# H22R2x_Frontend_1.net
KiCad netlist of a schematic drawn in Altium Designer
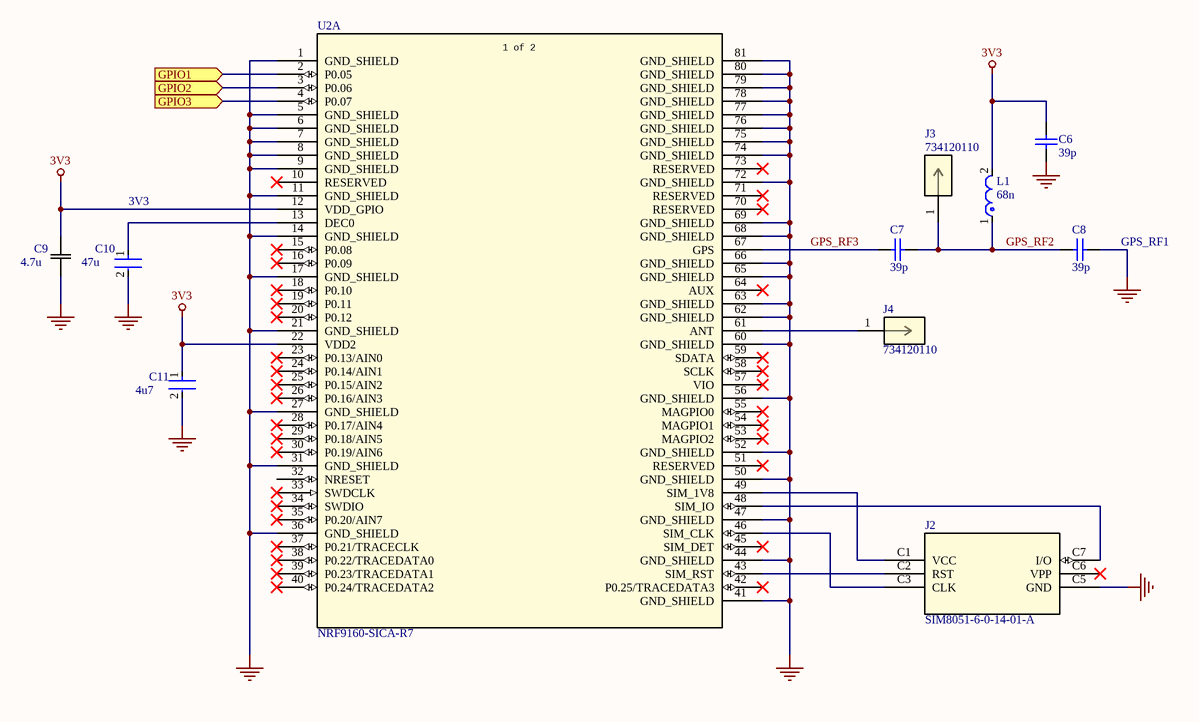
[diagram p0: H22R2x_Frontend 1.SchDoc]

(export (version "E")
  (design (tool "Eeschema 10.0.6"))
  (components
    (comp (ref "C6")
      (value "39p")
      (footprint "CAPC1005X56X25ML10T15")
      (description "04023A390KAT2A")
      (fields (field (name "MANUFACTURER") "AVX Interconnect / Elco"))
      (libsource (lib "Altium Content Vault") (part "CAP"))
    )
    (comp (ref "C7")
      (value "39p")
      (footprint "CAPC1005X56X25ML10T15")
      (description "04023A390KAT2A")
      (fields (field (name "MANUFACTURER") "AVX Interconnect / Elco"))
      (libsource (lib "Altium Content Vault") (part "CAP"))
    )
    (comp (ref "C8")
      (value "39p")
      (footprint "CAPC1005X56X25ML10T15")
      (description "04023A390KAT2A")
      (fields (field (name "MANUFACTURER") "AVX Interconnect / Elco"))
      (libsource (lib "Altium Content Vault") (part "CAP"))
    )
    (comp (ref "C9")
      (value "4.7u")
      (footprint "CAP_CL10_SAM")
      (description "4.7 µF ±10% 6.3V Ceramic Capacitor X5R 0603 (1608 Metric)")
      (fields
        (field (name "MANUFACTURER_PART_NUMBER") "CL10A475KQ8NNNC")
        (field (name "COPYRIGHT") "Copyright (C) 2025 Ultra Librarian. All rights reserved.")
      )
      (libsource (lib "Tyme Hopkins") (part "CL10A475KQ8NNNC"))
    )
    (comp (ref "C10")
      (value "47u")
      (footprint "FP-GRM21B-0_2-e0_2_0_7-IPC_B")
      (description "Chip Multilayer Ceramic Capacitors for General Purpose, 0805, 47uF, X5R, 15%, 20%, 6.3V")
      (fields (field (name "TOLERANCE") "20%"))
      (libsource (lib "Altium Content Vault") (part "b4654b650e69147ec39a6b967a45e02"))
    )
    (comp (ref "C11")
      (value "4u7")
      (footprint "FP-0603-L_1_6_0_15-W_0_8-MFG")
      (description "Ceramic Capacitor General Use 4.7uF ±10% 10V X6S 0603")
      (fields (field (name "TOLERANCE") "10%"))
      (libsource (lib "Altium Content Vault") (part "11868f565c42a9108669ba33697ecf6"))
    )
    (comp (ref "J2")
      (value "SIM8051-6-0-14-01-A")
      (footprint "SIM8051-6-0-14-01-A_GCT")
      (description "Description")
      (fields (field (name "COPYRIGHT") "Copyright (C) 2025 Ultra Librarian. All rights reserved."))
      (libsource (lib "Tyme Hopkins") (part "SIM8051-6-0-14-01-A"))
    )
    (comp (ref "J3")
      (value "734120110")
      (footprint "CONN_73412-0110_MOL")
      (description "MCRF Jack, Straight, PCB Receptacle, Surface Mount, 1.25mm Mounted Height, 50 Ohms")
      (fields (field (name "COPYRIGHT") "Copyright (C) 2025 Ultra Librarian. All rights reserved."))
      (libsource (lib "Tyme Hopkins") (part "734120110"))
    )
    (comp (ref "J4")
      (value "734120110")
      (footprint "CONN_73412-0110_MOL")
      (description "MCRF Jack, Straight, PCB Receptacle, Surface Mount, 1.25mm Mounted Height, 50 Ohms")
      (fields (field (name "COPYRIGHT") "Copyright (C) 2025 Ultra Librarian. All rights reserved."))
      (libsource (lib "") (part "734120110_1"))
    )
    (comp (ref "L1")
      (value "68n")
      (footprint "FP-LQG18HH_00-MFG")
      (description "Multilayer type RF Inductor 68nH ±5% 0.8Ω 400mA 0603\r\n\r\nLQG18HN68NJ00D")
      (fields (field (name "TOLERANCE") "5%"))
      (libsource (lib "Altium Content Vault") (part "4cc4b267dca4c8e51f7102f422741d8"))
    )
    (comp (ref "U2")
      (value "NRF9160-SICA-R7")
      (footprint "LGA127_16p00X10p50_nRF9160_NOR")
      (description "Description")
      (fields (field (name "COPYRIGHT") "Copyright (C) 2025 Ultra Librarian. All rights reserved."))
      (libsource (lib "Tyme Hopkins") (part "NRF9160-SICA-R7"))
    )
  )
  (nets
    (net (code "1") (name "/GPIO1") (class "Default")
      (node (ref "U2") (pin "2") (pinfunction "P0.05_2") (pintype "bidirectional"))
    )
    (net (code "2") (name "/GPIO2") (class "Default")
      (node (ref "U2") (pin "3") (pinfunction "P0.06_3") (pintype "bidirectional"))
    )
    (net (code "3") (name "/GPIO3") (class "Default")
      (node (ref "U2") (pin "4") (pinfunction "P0.07_4") (pintype "bidirectional"))
    )
    (net (code "4") (name "/GPS_RF2") (class "Default")
      (node (ref "C7") (pin "2") (pinfunction "2_2") (pintype "passive"))
      (node (ref "C8") (pin "1") (pinfunction "1_1") (pintype "passive"))
      (node (ref "J3") (pin "1") (pinfunction "1_1") (pintype "passive"))
      (node (ref "L1") (pin "1") (pinfunction "1_1") (pintype "passive"))
    )
    (net (code "5") (name "/GPS_RF3") (class "Default")
      (node (ref "C7") (pin "1") (pinfunction "1_1") (pintype "passive"))
      (node (ref "U2") (pin "67") (pinfunction "GPS_67") (pintype "passive"))
    )
    (net (code "6") (name "3V3") (class "Default")
      (node (ref "C11") (pin "1") (pinfunction "1_1") (pintype "passive"))
      (node (ref "C6") (pin "2") (pinfunction "2_2") (pintype "passive"))
      (node (ref "C9") (pin "2") (pinfunction "2_2") (pintype "passive"))
      (node (ref "L1") (pin "2") (pinfunction "2_2") (pintype "passive"))
      (node (ref "U2") (pin "12") (pinfunction "VDD_GPIO_12") (pintype "power_in"))
      (node (ref "U2") (pin "22") (pinfunction "VDD2_22") (pintype "power_in"))
    )
    (net (code "7") (name "GND") (class "Default")
      (node (ref "C10") (pin "2") (pinfunction "2_2") (pintype "passive"))
      (node (ref "C11") (pin "2") (pinfunction "2_2") (pintype "passive"))
      (node (ref "C6") (pin "1") (pinfunction "1_1") (pintype "passive"))
      (node (ref "C8") (pin "2") (pinfunction "2_2") (pintype "passive"))
      (node (ref "C9") (pin "1") (pinfunction "1_1") (pintype "passive"))
      (node (ref "J2") (pin "C5") (pinfunction "GND_C5") (pintype "power_in"))
      (node (ref "U2") (pin "1") (pinfunction "GND_SHIELD_1") (pintype "power_in"))
      (node (ref "U2") (pin "11") (pinfunction "GND_SHIELD_11") (pintype "power_in"))
      (node (ref "U2") (pin "14") (pinfunction "GND_SHIELD_14") (pintype "power_in"))
      (node (ref "U2") (pin "17") (pinfunction "GND_SHIELD_17") (pintype "power_in"))
      (node (ref "U2") (pin "21") (pinfunction "GND_SHIELD_21") (pintype "power_in"))
      (node (ref "U2") (pin "27") (pinfunction "GND_SHIELD_27") (pintype "power_in"))
      (node (ref "U2") (pin "31") (pinfunction "GND_SHIELD_31") (pintype "power_in"))
      (node (ref "U2") (pin "36") (pinfunction "GND_SHIELD_36") (pintype "power_in"))
      (node (ref "U2") (pin "41") (pinfunction "GND_SHIELD_41") (pintype "power_in"))
      (node (ref "U2") (pin "44") (pinfunction "GND_SHIELD_44") (pintype "power_in"))
      (node (ref "U2") (pin "47") (pinfunction "GND_SHIELD_47") (pintype "power_in"))
      (node (ref "U2") (pin "5") (pinfunction "GND_SHIELD_5") (pintype "power_in"))
      (node (ref "U2") (pin "50") (pinfunction "GND_SHIELD_50") (pintype "power_in"))
      (node (ref "U2") (pin "52") (pinfunction "GND_SHIELD_52") (pintype "power_in"))
      (node (ref "U2") (pin "56") (pinfunction "GND_SHIELD_56") (pintype "power_in"))
      (node (ref "U2") (pin "6") (pinfunction "GND_SHIELD_6") (pintype "power_in"))
      (node (ref "U2") (pin "60") (pinfunction "GND_SHIELD_60") (pintype "power_in"))
      (node (ref "U2") (pin "62") (pinfunction "GND_SHIELD_62") (pintype "power_in"))
      (node (ref "U2") (pin "63") (pinfunction "GND_SHIELD_63") (pintype "power_in"))
      (node (ref "U2") (pin "65") (pinfunction "GND_SHIELD_65") (pintype "power_in"))
      (node (ref "U2") (pin "66") (pinfunction "GND_SHIELD_66") (pintype "power_in"))
      (node (ref "U2") (pin "68") (pinfunction "GND_SHIELD_68") (pintype "power_in"))
      (node (ref "U2") (pin "69") (pinfunction "GND_SHIELD_69") (pintype "power_in"))
      (node (ref "U2") (pin "7") (pinfunction "GND_SHIELD_7") (pintype "power_in"))
      (node (ref "U2") (pin "72") (pinfunction "GND_SHIELD_72") (pintype "power_in"))
      (node (ref "U2") (pin "74") (pinfunction "GND_SHIELD_74") (pintype "power_in"))
      (node (ref "U2") (pin "75") (pinfunction "GND_SHIELD_75") (pintype "power_in"))
      (node (ref "U2") (pin "76") (pinfunction "GND_SHIELD_76") (pintype "power_in"))
      (node (ref "U2") (pin "77") (pinfunction "GND_SHIELD_77") (pintype "power_in"))
      (node (ref "U2") (pin "78") (pinfunction "GND_SHIELD_78") (pintype "power_in"))
      (node (ref "U2") (pin "79") (pinfunction "GND_SHIELD_79") (pintype "power_in"))
      (node (ref "U2") (pin "8") (pinfunction "GND_SHIELD_8") (pintype "power_in"))
      (node (ref "U2") (pin "80") (pinfunction "GND_SHIELD_80") (pintype "power_in"))
      (node (ref "U2") (pin "81") (pinfunction "GND_SHIELD_81") (pintype "power_in"))
      (node (ref "U2") (pin "9") (pinfunction "GND_SHIELD_9") (pintype "power_in"))
    )
    (net (code "8") (name "Net-(J2-CLK)") (class "Default")
      (node (ref "J2") (pin "C3") (pinfunction "CLK_C3") (pintype "passive"))
      (node (ref "U2") (pin "46") (pinfunction "SIM_CLK_46") (pintype "bidirectional"))
    )
    (net (code "9") (name "Net-(J2-I{slash}O)") (class "Default")
      (node (ref "J2") (pin "C7") (pinfunction "I/O_C7") (pintype "bidirectional"))
      (node (ref "U2") (pin "48") (pinfunction "SIM_IO_48") (pintype "bidirectional"))
    )
    (net (code "10") (name "Net-(J2-RST)") (class "Default")
      (node (ref "J2") (pin "C2") (pinfunction "RST_C2") (pintype "passive"))
      (node (ref "U2") (pin "43") (pinfunction "SIM_RST_43") (pintype "bidirectional"))
    )
    (net (code "11") (name "Net-(J2-VCC)") (class "Default")
      (node (ref "J2") (pin "C1") (pinfunction "VCC_C1") (pintype "power_in"))
      (node (ref "U2") (pin "49") (pinfunction "SIM_1V8_49") (pintype "power_in"))
    )
    (net (code "12") (name "Net-(U2A-ANT)") (class "Default")
      (node (ref "J4") (pin "1") (pinfunction "1_1") (pintype "passive"))
      (node (ref "U2") (pin "61") (pinfunction "ANT_61") (pintype "passive"))
    )
    (net (code "13") (name "Net-(U2A-DEC0)") (class "Default")
      (node (ref "C10") (pin "1") (pinfunction "1_1") (pintype "passive"))
      (node (ref "U2") (pin "13") (pinfunction "DEC0_13") (pintype "power_in"))
    )
    (net (code "14") (name "unconnected-(J2-VPP-PadC6)") (class "Default")
      (node (ref "J2") (pin "C6") (pinfunction "VPP_C6") (pintype "power_in+no_connect"))
    )
    (net (code "15") (name "unconnected-(U2A-AUX-Pad64)") (class "Default")
      (node (ref "U2") (pin "64") (pinfunction "AUX_64") (pintype "passive+no_connect"))
    )
    (net (code "16") (name "unconnected-(U2A-MAGPIO0-Pad55)") (class "Default")
      (node (ref "U2") (pin "55") (pinfunction "MAGPIO0_55") (pintype "bidirectional+no_connect"))
    )
    (net (code "17") (name "unconnected-(U2A-MAGPIO1-Pad54)") (class "Default")
      (node (ref "U2") (pin "54") (pinfunction "MAGPIO1_54") (pintype "bidirectional+no_connect"))
    )
    (net (code "18") (name "unconnected-(U2A-MAGPIO2-Pad53)") (class "Default")
      (node (ref "U2") (pin "53") (pinfunction "MAGPIO2_53") (pintype "bidirectional+no_connect"))
    )
    (net (code "19") (name "unconnected-(U2A-NRESET-Pad32)") (class "Default")
      (node (ref "U2") (pin "32") (pinfunction "NRESET_32") (pintype "bidirectional"))
    )
    (net (code "20") (name "unconnected-(U2A-P0.08-Pad15)") (class "Default")
      (node (ref "U2") (pin "15") (pinfunction "P0.08_15") (pintype "bidirectional+no_connect"))
    )
    (net (code "21") (name "unconnected-(U2A-P0.09-Pad16)") (class "Default")
      (node (ref "U2") (pin "16") (pinfunction "P0.09_16") (pintype "bidirectional+no_connect"))
    )
    (net (code "22") (name "unconnected-(U2A-P0.10-Pad18)") (class "Default")
      (node (ref "U2") (pin "18") (pinfunction "P0.10_18") (pintype "bidirectional+no_connect"))
    )
    (net (code "23") (name "unconnected-(U2A-P0.11-Pad19)") (class "Default")
      (node (ref "U2") (pin "19") (pinfunction "P0.11_19") (pintype "bidirectional+no_connect"))
    )
    (net (code "24") (name "unconnected-(U2A-P0.12-Pad20)") (class "Default")
      (node (ref "U2") (pin "20") (pinfunction "P0.12_20") (pintype "bidirectional+no_connect"))
    )
    (net (code "25") (name "unconnected-(U2A-P0.13{slash}AIN0-Pad23)") (class "Default")
      (node (ref "U2") (pin "23") (pinfunction "P0.13/AIN0_23") (pintype "bidirectional+no_connect"))
    )
    (net (code "26") (name "unconnected-(U2A-P0.14{slash}AIN1-Pad24)") (class "Default")
      (node (ref "U2") (pin "24") (pinfunction "P0.14/AIN1_24") (pintype "bidirectional+no_connect"))
    )
    (net (code "27") (name "unconnected-(U2A-P0.15{slash}AIN2-Pad25)") (class "Default")
      (node (ref "U2") (pin "25") (pinfunction "P0.15/AIN2_25") (pintype "bidirectional+no_connect"))
    )
    (net (code "28") (name "unconnected-(U2A-P0.16{slash}AIN3-Pad26)") (class "Default")
      (node (ref "U2") (pin "26") (pinfunction "P0.16/AIN3_26") (pintype "bidirectional+no_connect"))
    )
    (net (code "29") (name "unconnected-(U2A-P0.17{slash}AIN4-Pad28)") (class "Default")
      (node (ref "U2") (pin "28") (pinfunction "P0.17/AIN4_28") (pintype "bidirectional+no_connect"))
    )
    (net (code "30") (name "unconnected-(U2A-P0.18{slash}AIN5-Pad29)") (class "Default")
      (node (ref "U2") (pin "29") (pinfunction "P0.18/AIN5_29") (pintype "bidirectional+no_connect"))
    )
    (net (code "31") (name "unconnected-(U2A-P0.19{slash}AIN6-Pad30)") (class "Default")
      (node (ref "U2") (pin "30") (pinfunction "P0.19/AIN6_30") (pintype "bidirectional+no_connect"))
    )
    (net (code "32") (name "unconnected-(U2A-P0.20{slash}AIN7-Pad35)") (class "Default")
      (node (ref "U2") (pin "35") (pinfunction "P0.20/AIN7_35") (pintype "bidirectional+no_connect"))
    )
    (net (code "33") (name "unconnected-(U2A-P0.21{slash}TRACECLK-Pad37)") (class "Default")
      (node (ref "U2") (pin "37") (pinfunction "P0.21/TRACECLK_37") (pintype "bidirectional+no_connect"))
    )
    (net (code "34") (name "unconnected-(U2A-P0.22{slash}TRACEDATA0-Pad38)") (class "Default")
      (node (ref "U2") (pin "38") (pinfunction "P0.22/TRACEDATA0_38") (pintype "bidirectional+no_connect"))
    )
    (net (code "35") (name "unconnected-(U2A-P0.23{slash}TRACEDATA1-Pad39)") (class "Default")
      (node (ref "U2") (pin "39") (pinfunction "P0.23/TRACEDATA1_39") (pintype "bidirectional+no_connect"))
    )
    (net (code "36") (name "unconnected-(U2A-P0.24{slash}TRACEDATA2-Pad40)") (class "Default")
      (node (ref "U2") (pin "40") (pinfunction "P0.24/TRACEDATA2_40") (pintype "bidirectional+no_connect"))
    )
    (net (code "37") (name "unconnected-(U2A-P0.25{slash}TRACEDATA3-Pad42)") (class "Default")
      (node (ref "U2") (pin "42") (pinfunction "P0.25/TRACEDATA3_42") (pintype "bidirectional+no_connect"))
    )
    (net (code "38") (name "unconnected-(U2A-RESERVED-Pad10)") (class "Default")
      (node (ref "U2") (pin "10") (pinfunction "RESERVED_10") (pintype "passive+no_connect"))
    )
    (net (code "39") (name "unconnected-(U2A-RESERVED-Pad51)") (class "Default")
      (node (ref "U2") (pin "51") (pinfunction "RESERVED_51") (pintype "passive+no_connect"))
    )
    (net (code "40") (name "unconnected-(U2A-RESERVED-Pad70)") (class "Default")
      (node (ref "U2") (pin "70") (pinfunction "RESERVED_70") (pintype "passive+no_connect"))
    )
    (net (code "41") (name "unconnected-(U2A-RESERVED-Pad71)") (class "Default")
      (node (ref "U2") (pin "71") (pinfunction "RESERVED_71") (pintype "passive+no_connect"))
    )
    (net (code "42") (name "unconnected-(U2A-RESERVED-Pad73)") (class "Default")
      (node (ref "U2") (pin "73") (pinfunction "RESERVED_73") (pintype "passive+no_connect"))
    )
    (net (code "43") (name "unconnected-(U2A-SCLK-Pad58)") (class "Default")
      (node (ref "U2") (pin "58") (pinfunction "SCLK_58") (pintype "bidirectional+no_connect"))
    )
    (net (code "44") (name "unconnected-(U2A-SDATA-Pad59)") (class "Default")
      (node (ref "U2") (pin "59") (pinfunction "SDATA_59") (pintype "bidirectional+no_connect"))
    )
    (net (code "45") (name "unconnected-(U2A-SIM_DET-Pad45)") (class "Default")
      (node (ref "U2") (pin "45") (pinfunction "SIM_DET_45") (pintype "bidirectional+no_connect"))
    )
    (net (code "46") (name "unconnected-(U2A-SWDCLK-Pad33)") (class "Default")
      (node (ref "U2") (pin "33") (pinfunction "SWDCLK_33") (pintype "input+no_connect"))
    )
    (net (code "47") (name "unconnected-(U2A-SWDIO-Pad34)") (class "Default")
      (node (ref "U2") (pin "34") (pinfunction "SWDIO_34") (pintype "bidirectional+no_connect"))
    )
    (net (code "48") (name "unconnected-(U2A-VIO-Pad57)") (class "Default")
      (node (ref "U2") (pin "57") (pinfunction "VIO_57") (pintype "power_in+no_connect"))
    )
  )
)
